# Thermostat.net
KiCad netlist of a schematic drawn in Altium Designer
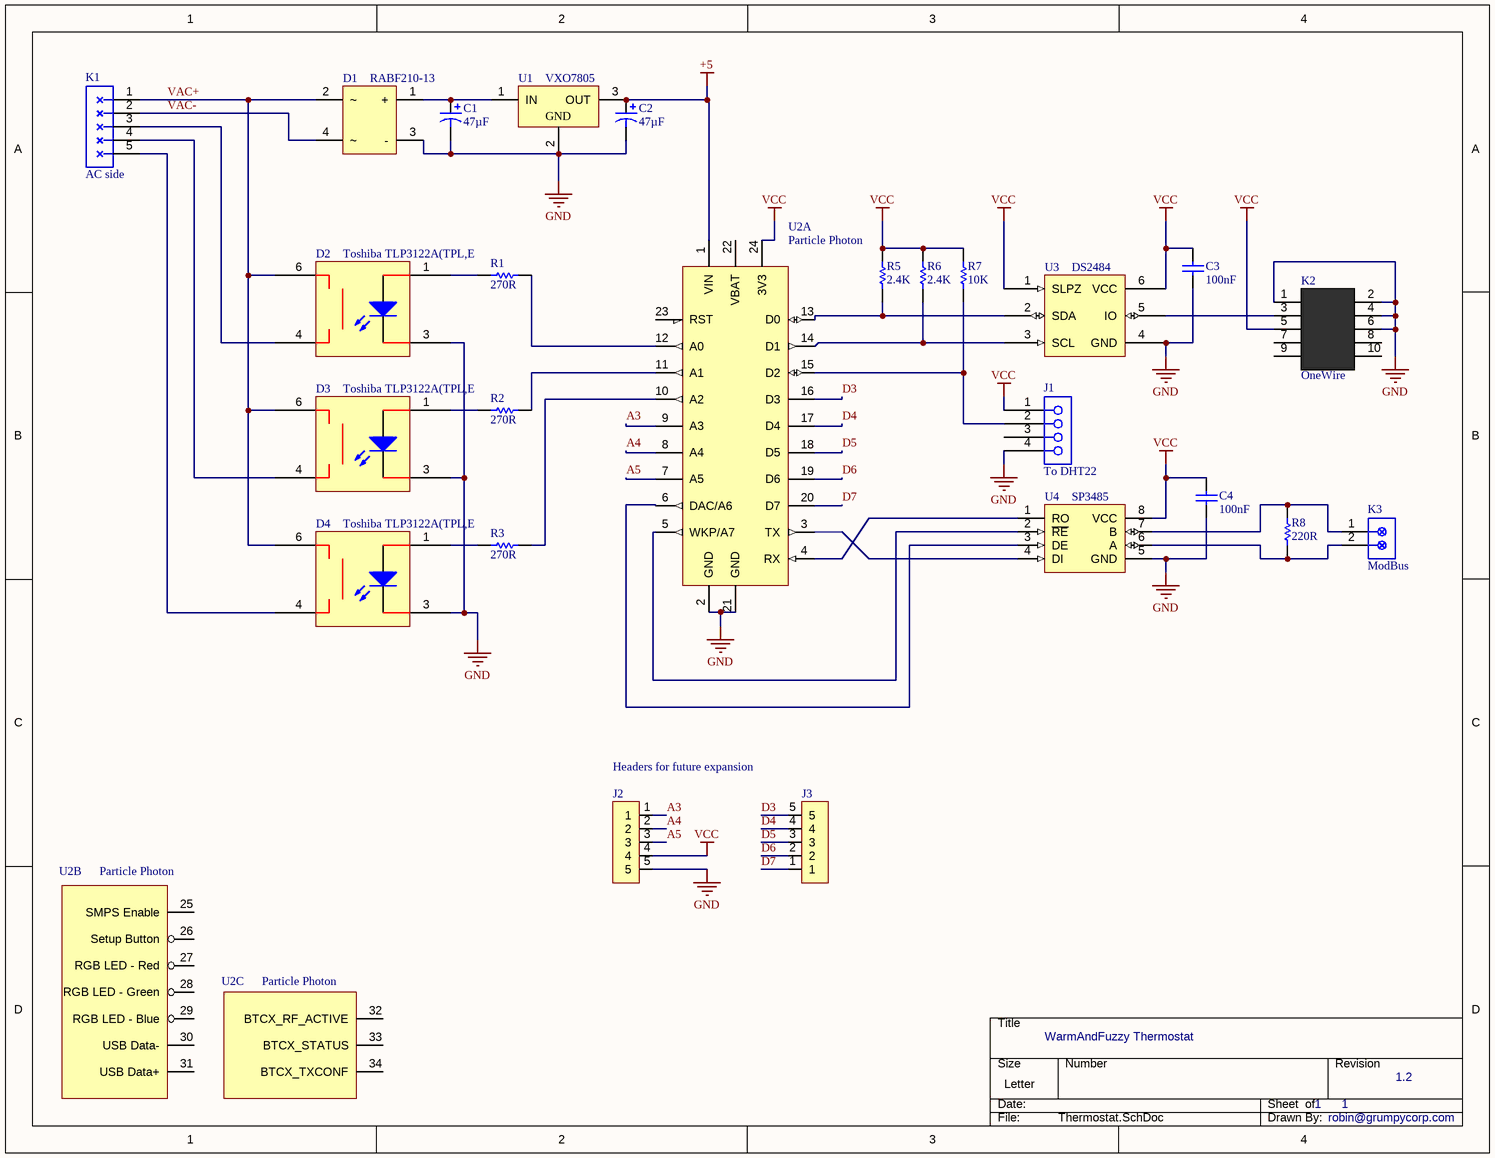
[diagram p0: Thermostat.SchDoc]

(export (version "E")
  (design (tool "Eeschema 10.0.6"))
  (components
    (comp (ref "C1")
      (value "47µF")
      (footprint "ELCO-6.3-12-2.5")
      (description "47uF 63 V dc Aluminium Electrolytic Capacitor, VR Series 2000h 6.3 (Dia.) x 11mm")
      (fields (field (name "MANUFACTURER PART NUMBER") "UVR1J470MED"))
      (libsource (lib "CommunityVault") (part "CMP-5ae993e06a1d852e-2"))
    )
    (comp (ref "C2")
      (value "47µF")
      (footprint "ELCO-6.3-12-2.5")
      (description "47uF 63 V dc Aluminium Electrolytic Capacitor, VR Series 2000h 6.3 (Dia.) x 11mm")
      (fields (field (name "MANUFACTURER PART NUMBER") "UVR1J470MED"))
      (libsource (lib "CommunityVault") (part "CMP-5ae993e06a1d852e-2"))
    )
    (comp (ref "C3")
      (value "100nF")
      (footprint "PCB-57eb66w7n7cajp6rs5yy-1")
      (description "Cap, Mlcc, X7r, 0.1Uf, 100V, 0805")
      (fields (field (name "MANUFACTURER PART NUMBER") "885012207128"))
      (libsource (lib "CommunityVault") (part "CMP-7da2b1f9736fa265-1"))
    )
    (comp (ref "C4")
      (value "100nF")
      (footprint "PCB-57eb66w7n7cajp6rs5yy-1")
      (description "Cap, Mlcc, X7r, 0.1Uf, 100V, 0805")
      (fields (field (name "MANUFACTURER PART NUMBER") "885012207128"))
      (libsource (lib "CommunityVault") (part "CMP-7da2b1f9736fa265-1"))
    )
    (comp (ref "D1")
      (value "RABF210-13")
      (footprint "PCB-a4f1j7dljjmb9y4t2o4h-1")
      (description "Bridge Rectifier ABF/SOPA-4 Type")
      (libsource (lib "CommunityVault") (part "CMP-b47278e240476bb5-3"))
    )
    (comp (ref "D2")
      (value "Toshiba TLP3122A(TPL,E")
      (footprint "PCBComponent_1")
      (description "Relay Ssr 25MA 1.4V Dc-in Dc-out 4-PIN So T/r")
      (fields (field (name "MANUFACTURER PART NUMBER") "TLP3122A(TPL,E"))
      (libsource (lib "CommunityVault") (part "CMP-0758cb201e08d89f-2"))
    )
    (comp (ref "D3")
      (value "Toshiba TLP3122A(TPL,E")
      (footprint "PCBComponent_1")
      (description "Relay Ssr 25MA 1.4V Dc-in Dc-out 4-PIN So T/r")
      (fields (field (name "MANUFACTURER PART NUMBER") "TLP3122A(TPL,E"))
      (libsource (lib "CommunityVault") (part "CMP-0758cb201e08d89f-2"))
    )
    (comp (ref "D4")
      (value "Toshiba TLP3122A(TPL,E")
      (footprint "PCBComponent_1")
      (description "Relay Ssr 25MA 1.4V Dc-in Dc-out 4-PIN So T/r")
      (fields (field (name "MANUFACTURER PART NUMBER") "TLP3122A(TPL,E"))
      (libsource (lib "CommunityVault") (part "CMP-0758cb201e08d89f-2"))
    )
    (comp (ref "J1")
      (value "To DHT22")
      (footprint "PCB-rn7un5c8cc0swpp1289c-1")
      (description "Conn Unshrouded Header HDR 4 POS 2.54mm Solder ST Thru-Hole")
      (libsource (lib "CommunityVault") (part "CMP-64ffaf704303bb38-11"))
    )
    (comp (ref "J2")
      (value "Future")
      (footprint "PCB-rnlen50cc5tt6vc22c1r-1")
      (description "MTA-100 5 Position Through-Hole Single Row Straight Wire to Board Header")
      (fields (field (name "MANUFACTURER PART NUMBER") "3-644456-5"))
      (libsource (lib "CommunityVault") (part "CMP-b5d67e8662e76a11-19"))
    )
    (comp (ref "J3")
      (value "Future")
      (footprint "PCB-rnlen50cc5tt6vc22c1r-1")
      (description "MTA-100 5 Position Through-Hole Single Row Straight Wire to Board Header")
      (fields (field (name "MANUFACTURER PART NUMBER") "3-644456-5"))
      (libsource (lib "") (part "CMP-b5d67e8662e76a11-19_1"))
    )
    (comp (ref "K1")
      (value "AC side")
      (footprint "PCB-pdjdo99g3kfsve06mxjg-1")
      (description "Series 1377 - 5.00 mm Horizontal Entry with Pressure Clamp WR-TBL, 5 pin")
      (fields (field (name "MANUFACTURER PART NUMBER") "691137710005"))
      (libsource (lib "CommunityVault") (part "CMP-bd1670afe21562d1-1"))
    )
    (comp (ref "K2")
      (value "OneWire")
      (footprint "PCB-aez6wowwcq4hxfvji4nz-1")
      (description "Conn Shrouded Header HDR 10 POS 2.54mm Solder ST Thru-Hole")
      (fields
        (field (name "MANUFACTURER") "On Shore Technology")
        (field (name "MANUFACTURER PART NUMBER") "302-S101")
      )
      (libsource (lib "CommunityVault") (part "CMP-7037b818d660aff0-6"))
    )
    (comp (ref "K3")
      (value "ModBus")
      (footprint "PCBComponent_1")
      (description "Series 1377 - 5.00 mm Horizontal Entry with Pressure Clamp WR-TBL, 2 pin")
      (fields (field (name "MANUFACTURER PART NUMBER") "691137710002"))
      (libsource (lib "CommunityVault") (part "CMP-e1e12c58bed83e26-3"))
    )
    (comp (ref "R1")
      (value "270R")
      (footprint "RESC2012X50N")
      (description "Thick film resistor")
      (fields (field (name "MANUFACTURER PART NUMBER") "CRCW0805270RFKEA"))
      (libsource (lib "CommunityVault") (part "CMP-10770253-6"))
    )
    (comp (ref "R2")
      (value "270R")
      (footprint "RESC2012X50N")
      (description "Thick film resistor")
      (fields (field (name "MANUFACTURER PART NUMBER") "CRCW0805270RFKEA"))
      (libsource (lib "CommunityVault") (part "CMP-10770253-6"))
    )
    (comp (ref "R3")
      (value "270R")
      (footprint "RESC2012X50N")
      (description "Thick film resistor")
      (fields (field (name "MANUFACTURER PART NUMBER") "CRCW0805270RFKEA"))
      (libsource (lib "CommunityVault") (part "CMP-10770253-6"))
    )
    (comp (ref "R5")
      (value "2.4K")
      (footprint "RESC2013X70X40ML20T20")
      (description "Thick Film Resistors - SMD 0805 2.4Kohms 5% Tol")
      (fields (field (name "MANUFACTURER PART NUMBER") "ERJ-6GEYJ242V"))
      (libsource (lib "CommunityVault") (part "CMP-3674929-2"))
    )
    (comp (ref "R6")
      (value "2.4K")
      (footprint "RESC2013X70X40ML20T20")
      (description "Thick Film Resistors - SMD 0805 2.4Kohms 5% Tol")
      (fields (field (name "MANUFACTURER PART NUMBER") "ERJ-6GEYJ242V"))
      (libsource (lib "CommunityVault") (part "CMP-3674929-2"))
    )
    (comp (ref "R7")
      (value "10K")
      (footprint "PCB-7wrvqjq7seaxrusqyahf-1")
      (description "Res Thin Film 0805 10K Ohm 0.1% 1/10W ±25ppm/°C Molded SMD SMD Paper T/R")
      (fields (field (name "MANUFACTURER PART NUMBER") "CPF0805B10KE"))
      (libsource (lib "CommunityVault") (part "CMP-ce7e062e016b11b9-3"))
    )
    (comp (ref "R8")
      (value "220R")
      (footprint "PCB-iya84cdbm96dhb72y1ru-1")
      (description "Res Thick Film 0805 220 Ohm 1% 1/8W ±100ppm/°C Molded SMD SMD Paper T/R")
      (fields (field (name "MANUFACTURER PART NUMBER") "CRCW0805220RFKEA"))
      (libsource (lib "CommunityVault") (part "CMP-3828968-6"))
    )
    (comp (ref "U1")
      (value "VXO7805")
      (footprint "TO220")
      (description "VXO78-1000 Series 24 / 12 Vin ±5 Vout Non-Isolated DC Switching Regulator")
      (fields (field (name "MANUFACTURER PART NUMBER") "VXO7805-1000"))
      (libsource (lib "CommunityVault") (part "CMP-591094eba19486d7-3"))
    )
    (comp (ref "U2")
      (value "Particle Photon")
      (footprint "PCBComponent_1 - duplicate")
      (description "Particle Photon with Headers")
      (libsource (lib "CommunityVault") (part "CMP-bf527286d3196095-5"))
    )
    (comp (ref "U3")
      (value "DS2484")
      (footprint "SOP6")
      (description "Single Channel 1-Wire Master 6-Pin SOT-23 T/R")
      (fields (field (name "MANUFACTURER PART NUMBER") "DS2484R+T"))
      (libsource (lib "CommunityVault") (part "CMP-0ec0c6075a5bd107-2"))
    )
    (comp (ref "U4")
      (value "SP3485")
      (footprint "PCB-1k2z6ddivtd17xu2xxf0-1")
      (description "SP3485 Series 10 Mbps 3.3 V Low Power Half Duplex RS-485 Transceiver - SOIC-8N")
      (fields (field (name "MANUFACTURER PART NUMBER") "SP3485EN-L"))
      (libsource (lib "CommunityVault") (part "CMP-69cfa0afed5fb608-2"))
    )
  )
  (nets
    (net (code "1") (name "+5") (class "Default")
      (node (ref "C2") (pin "1") (pinfunction "1_1") (pintype "passive"))
      (node (ref "U1") (pin "3") (pinfunction "OUT_3") (pintype "power_in"))
      (node (ref "U2") (pin "1") (pinfunction "VIN_1") (pintype "power_in"))
    )
    (net (code "2") (name "/A3") (class "Default")
      (node (ref "J2") (pin "1") (pinfunction "1_1") (pintype "passive"))
      (node (ref "U2") (pin "9") (pinfunction "A3_9") (pintype "passive"))
    )
    (net (code "3") (name "/A4") (class "Default")
      (node (ref "J2") (pin "2") (pinfunction "2_2") (pintype "passive"))
      (node (ref "U2") (pin "8") (pinfunction "A4_8") (pintype "passive"))
    )
    (net (code "4") (name "/A5") (class "Default")
      (node (ref "J2") (pin "3") (pinfunction "3_3") (pintype "passive"))
      (node (ref "U2") (pin "7") (pinfunction "A5_7") (pintype "passive"))
    )
    (net (code "5") (name "/D3") (class "Default")
      (node (ref "J3") (pin "5") (pinfunction "5_5") (pintype "passive"))
      (node (ref "U2") (pin "16") (pinfunction "D3_16") (pintype "passive"))
    )
    (net (code "6") (name "/D4") (class "Default")
      (node (ref "J3") (pin "4") (pinfunction "4_4") (pintype "passive"))
      (node (ref "U2") (pin "17") (pinfunction "D4_17") (pintype "passive"))
    )
    (net (code "7") (name "/D5") (class "Default")
      (node (ref "J3") (pin "3") (pinfunction "3_3") (pintype "passive"))
      (node (ref "U2") (pin "18") (pinfunction "D5_18") (pintype "passive"))
    )
    (net (code "8") (name "/D6") (class "Default")
      (node (ref "J3") (pin "2") (pinfunction "2_2") (pintype "passive"))
      (node (ref "U2") (pin "19") (pinfunction "D6_19") (pintype "passive"))
    )
    (net (code "9") (name "/D7") (class "Default")
      (node (ref "J3") (pin "1") (pinfunction "1_1") (pintype "passive"))
      (node (ref "U2") (pin "20") (pinfunction "D7_20") (pintype "passive"))
    )
    (net (code "10") (name "/VAC+") (class "Default")
      (node (ref "D1") (pin "2") (pinfunction "~_2") (pintype "passive"))
      (node (ref "D2") (pin "6") (pintype "passive"))
      (node (ref "D3") (pin "6") (pintype "passive"))
      (node (ref "D4") (pin "6") (pintype "passive"))
      (node (ref "K1") (pin "1") (pinfunction "1_1") (pintype "passive"))
    )
    (net (code "11") (name "/VAC-") (class "Default")
      (node (ref "D1") (pin "4") (pinfunction "~_4") (pintype "passive"))
      (node (ref "K1") (pin "2") (pinfunction "2_2") (pintype "passive"))
    )
    (net (code "12") (name "GND") (class "Default")
      (node (ref "C1") (pin "2") (pinfunction "2_2") (pintype "passive"))
      (node (ref "C2") (pin "2") (pinfunction "2_2") (pintype "passive"))
      (node (ref "C3") (pin "1") (pinfunction "1_1") (pintype "passive"))
      (node (ref "C4") (pin "1") (pinfunction "1_1") (pintype "passive"))
      (node (ref "D1") (pin "3") (pinfunction "-_3") (pintype "passive"))
      (node (ref "D2") (pin "3") (pintype "passive"))
      (node (ref "D3") (pin "3") (pintype "passive"))
      (node (ref "D4") (pin "3") (pintype "passive"))
      (node (ref "J1") (pin "4") (pinfunction "4_4") (pintype "passive"))
      (node (ref "J2") (pin "5") (pinfunction "5_5") (pintype "passive"))
      (node (ref "K2") (pin "1") (pinfunction "1_1") (pintype "passive"))
      (node (ref "K2") (pin "2") (pinfunction "2_2") (pintype "passive"))
      (node (ref "K2") (pin "4") (pinfunction "4_4") (pintype "passive"))
      (node (ref "K2") (pin "6") (pinfunction "6_6") (pintype "passive"))
      (node (ref "U1") (pin "2") (pinfunction "GND_2") (pintype "power_in"))
      (node (ref "U2") (pin "2") (pinfunction "GND_2") (pintype "power_in"))
      (node (ref "U2") (pin "21") (pinfunction "GND_21") (pintype "power_in"))
      (node (ref "U3") (pin "4") (pinfunction "GND_4") (pintype "power_in"))
      (node (ref "U4") (pin "5") (pinfunction "GND_5") (pintype "power_in"))
    )
    (net (code "13") (name "Net-(D1-+)") (class "Default")
      (node (ref "C1") (pin "1") (pinfunction "1_1") (pintype "passive"))
      (node (ref "D1") (pin "1") (pinfunction "+_1") (pintype "passive"))
      (node (ref "U1") (pin "1") (pinfunction "IN_1") (pintype "power_in"))
    )
    (net (code "14") (name "Net-(D2-Pad1)") (class "Default")
      (node (ref "D2") (pin "1") (pintype "passive"))
      (node (ref "R1") (pin "1") (pinfunction "1_1") (pintype "passive"))
    )
    (net (code "15") (name "Net-(D2-Pad4)") (class "Default")
      (node (ref "D2") (pin "4") (pintype "passive"))
      (node (ref "K1") (pin "3") (pinfunction "3_3") (pintype "passive"))
    )
    (net (code "16") (name "Net-(D3-Pad1)") (class "Default")
      (node (ref "D3") (pin "1") (pintype "passive"))
      (node (ref "R2") (pin "1") (pinfunction "1_1") (pintype "passive"))
    )
    (net (code "17") (name "Net-(D3-Pad4)") (class "Default")
      (node (ref "D3") (pin "4") (pintype "passive"))
      (node (ref "K1") (pin "4") (pinfunction "4_4") (pintype "passive"))
    )
    (net (code "18") (name "Net-(D4-Pad1)") (class "Default")
      (node (ref "D4") (pin "1") (pintype "passive"))
      (node (ref "R3") (pin "1") (pinfunction "1_1") (pintype "passive"))
    )
    (net (code "19") (name "Net-(D4-Pad4)") (class "Default")
      (node (ref "D4") (pin "4") (pintype "passive"))
      (node (ref "K1") (pin "5") (pinfunction "5_5") (pintype "passive"))
    )
    (net (code "20") (name "Net-(U2A-A0)") (class "Default")
      (node (ref "R1") (pin "2") (pinfunction "2_2") (pintype "passive"))
      (node (ref "U2") (pin "12") (pinfunction "A0_12") (pintype "output"))
    )
    (net (code "21") (name "Net-(U2A-A1)") (class "Default")
      (node (ref "R2") (pin "2") (pinfunction "2_2") (pintype "passive"))
      (node (ref "U2") (pin "11") (pinfunction "A1_11") (pintype "output"))
    )
    (net (code "22") (name "Net-(U2A-A2)") (class "Default")
      (node (ref "R3") (pin "2") (pinfunction "2_2") (pintype "passive"))
      (node (ref "U2") (pin "10") (pinfunction "A2_10") (pintype "output"))
    )
    (net (code "23") (name "Net-(U2A-D0)") (class "Default")
      (node (ref "R5") (pin "1") (pinfunction "1_1") (pintype "passive"))
      (node (ref "U2") (pin "13") (pinfunction "D0_13") (pintype "bidirectional"))
      (node (ref "U3") (pin "2") (pinfunction "SDA_2") (pintype "bidirectional"))
    )
    (net (code "24") (name "Net-(U2A-D1)") (class "Default")
      (node (ref "R6") (pin "1") (pinfunction "1_1") (pintype "passive"))
      (node (ref "U2") (pin "14") (pinfunction "D1_14") (pintype "output"))
      (node (ref "U3") (pin "3") (pinfunction "SCL_3") (pintype "input"))
    )
    (net (code "25") (name "Net-(U2A-D2)") (class "Default")
      (node (ref "J1") (pin "2") (pinfunction "2_2") (pintype "passive"))
      (node (ref "R7") (pin "2") (pinfunction "2_2") (pintype "passive"))
      (node (ref "U2") (pin "15") (pinfunction "D2_15") (pintype "bidirectional"))
    )
    (net (code "26") (name "Net-(U2A-DAC{slash}A6)") (class "Default")
      (node (ref "U2") (pin "6") (pinfunction "DAC/A6_6") (pintype "output"))
      (node (ref "U4") (pin "3") (pinfunction "DE_3") (pintype "input"))
    )
    (net (code "27") (name "Net-(U2A-RX)") (class "Default")
      (node (ref "U2") (pin "4") (pinfunction "RX_4") (pintype "input"))
      (node (ref "U4") (pin "1") (pinfunction "RO_1") (pintype "tri_state"))
    )
    (net (code "28") (name "Net-(U2A-TX)") (class "Default")
      (node (ref "U2") (pin "3") (pinfunction "TX_3") (pintype "output"))
      (node (ref "U4") (pin "4") (pinfunction "DI_4") (pintype "input"))
    )
    (net (code "29") (name "Net-(U2A-WKP{slash}A7)") (class "Default")
      (node (ref "U2") (pin "5") (pinfunction "WKP/A7_5") (pintype "output"))
      (node (ref "U4") (pin "2") (pinfunction "~{RE}_2") (pintype "input"))
    )
    (net (code "30") (name "Net-(U3-IO)") (class "Default")
      (node (ref "K2") (pin "3") (pinfunction "3_3") (pintype "passive"))
      (node (ref "U3") (pin "5") (pinfunction "IO_5") (pintype "bidirectional"))
    )
    (net (code "31") (name "Net-(U4-A)") (class "Default")
      (node (ref "K3") (pin "2") (pinfunction "2_2") (pintype "passive"))
      (node (ref "R8") (pin "1") (pinfunction "1_1") (pintype "passive"))
      (node (ref "U4") (pin "6") (pinfunction "A_6") (pintype "bidirectional"))
    )
    (net (code "32") (name "Net-(U4-B)") (class "Default")
      (node (ref "K3") (pin "1") (pinfunction "1_1") (pintype "passive"))
      (node (ref "R8") (pin "2") (pinfunction "2_2") (pintype "passive"))
      (node (ref "U4") (pin "7") (pinfunction "B_7") (pintype "bidirectional"))
    )
    (net (code "33") (name "VCC") (class "Default")
      (node (ref "C3") (pin "2") (pinfunction "2_2") (pintype "passive"))
      (node (ref "C4") (pin "2") (pinfunction "2_2") (pintype "passive"))
      (node (ref "J1") (pin "1") (pinfunction "1_1") (pintype "passive"))
      (node (ref "J2") (pin "4") (pinfunction "4_4") (pintype "passive"))
      (node (ref "K2") (pin "5") (pinfunction "5_5") (pintype "passive"))
      (node (ref "R5") (pin "2") (pinfunction "2_2") (pintype "passive"))
      (node (ref "R6") (pin "2") (pinfunction "2_2") (pintype "passive"))
      (node (ref "R7") (pin "1") (pinfunction "1_1") (pintype "passive"))
      (node (ref "U2") (pin "24") (pinfunction "3V3_24") (pintype "power_in"))
      (node (ref "U3") (pin "1") (pinfunction "SLPZ_1") (pintype "input"))
      (node (ref "U3") (pin "6") (pinfunction "VCC_6") (pintype "power_in"))
      (node (ref "U4") (pin "8") (pinfunction "VCC_8") (pintype "power_in"))
    )
    (net (code "34") (name "unconnected-(D2-A-Pad)") (class "Default")
      (node (ref "D2") (pin "") (pinfunction "A_") (pintype "passive"))
    )
    (net (code "35") (name "unconnected-(D2-K-Pad)") (class "Default")
      (node (ref "D2") (pin "") (pinfunction "K_") (pintype "passive"))
    )
    (net (code "36") (name "unconnected-(D3-A-Pad)") (class "Default")
      (node (ref "D3") (pin "") (pinfunction "A_") (pintype "passive"))
    )
    (net (code "37") (name "unconnected-(D3-K-Pad)") (class "Default")
      (node (ref "D3") (pin "") (pinfunction "K_") (pintype "passive"))
    )
    (net (code "38") (name "unconnected-(D4-A-Pad)") (class "Default")
      (node (ref "D4") (pin "") (pinfunction "A_") (pintype "passive"))
    )
    (net (code "39") (name "unconnected-(D4-K-Pad)") (class "Default")
      (node (ref "D4") (pin "") (pinfunction "K_") (pintype "passive"))
    )
    (net (code "40") (name "unconnected-(J1-Pad3)") (class "Default")
      (node (ref "J1") (pin "3") (pinfunction "3_3") (pintype "passive"))
    )
    (net (code "41") (name "unconnected-(K2-Pad7)") (class "Default")
      (node (ref "K2") (pin "7") (pinfunction "7_7") (pintype "passive"))
    )
    (net (code "42") (name "unconnected-(K2-Pad8)") (class "Default")
      (node (ref "K2") (pin "8") (pinfunction "8_8") (pintype "passive"))
    )
    (net (code "43") (name "unconnected-(K2-Pad9)") (class "Default")
      (node (ref "K2") (pin "9") (pinfunction "9_9") (pintype "passive"))
    )
    (net (code "44") (name "unconnected-(K2-Pad10)") (class "Default")
      (node (ref "K2") (pin "10") (pinfunction "10_10") (pintype "passive"))
    )
    (net (code "45") (name "unconnected-(U2A-RST-Pad23)") (class "Default")
      (node (ref "U2") (pin "23") (pinfunction "RST_23") (pintype "passive"))
    )
    (net (code "46") (name "unconnected-(U2A-VBAT-Pad22)") (class "Default")
      (node (ref "U2") (pin "22") (pinfunction "VBAT_22") (pintype "power_in"))
    )
    (net (code "47") (name "unconnected-(U2B-RGB_LED_-_Blue-Pad29)") (class "Default")
      (node (ref "U2") (pin "29") (pinfunction "RGB_LED_-_Blue_29") (pintype "passive"))
    )
    (net (code "48") (name "unconnected-(U2B-RGB_LED_-_Green-Pad28)") (class "Default")
      (node (ref "U2") (pin "28") (pinfunction "RGB_LED_-_Green_28") (pintype "passive"))
    )
    (net (code "49") (name "unconnected-(U2B-RGB_LED_-_Red-Pad27)") (class "Default")
      (node (ref "U2") (pin "27") (pinfunction "RGB_LED_-_Red_27") (pintype "passive"))
    )
    (net (code "50") (name "unconnected-(U2B-SMPS_Enable-Pad25)") (class "Default")
      (node (ref "U2") (pin "25") (pinfunction "SMPS_Enable_25") (pintype "passive"))
    )
    (net (code "51") (name "unconnected-(U2B-Setup_Button-Pad26)") (class "Default")
      (node (ref "U2") (pin "26") (pinfunction "Setup_Button_26") (pintype "passive"))
    )
    (net (code "52") (name "unconnected-(U2B-USB_Data+-Pad31)") (class "Default")
      (node (ref "U2") (pin "31") (pinfunction "USB_Data+_31") (pintype "passive"))
    )
    (net (code "53") (name "unconnected-(U2B-USB_Data--Pad30)") (class "Default")
      (node (ref "U2") (pin "30") (pinfunction "USB_Data-_30") (pintype "passive"))
    )
    (net (code "54") (name "unconnected-(U2C-BTCX_RF_ACTIVE-Pad32)") (class "Default")
      (node (ref "U2") (pin "32") (pinfunction "BTCX_RF_ACTIVE_32") (pintype "tri_state"))
    )
    (net (code "55") (name "unconnected-(U2C-BTCX_STATUS-Pad33)") (class "Default")
      (node (ref "U2") (pin "33") (pinfunction "BTCX_STATUS_33") (pintype "tri_state"))
    )
    (net (code "56") (name "unconnected-(U2C-BTCX_TXCONF-Pad34)") (class "Default")
      (node (ref "U2") (pin "34") (pinfunction "BTCX_TXCONF_34") (pintype "tri_state"))
    )
  )
)
